# 20-Zigbee.net
KiCad netlist of a schematic drawn in Altium Designer
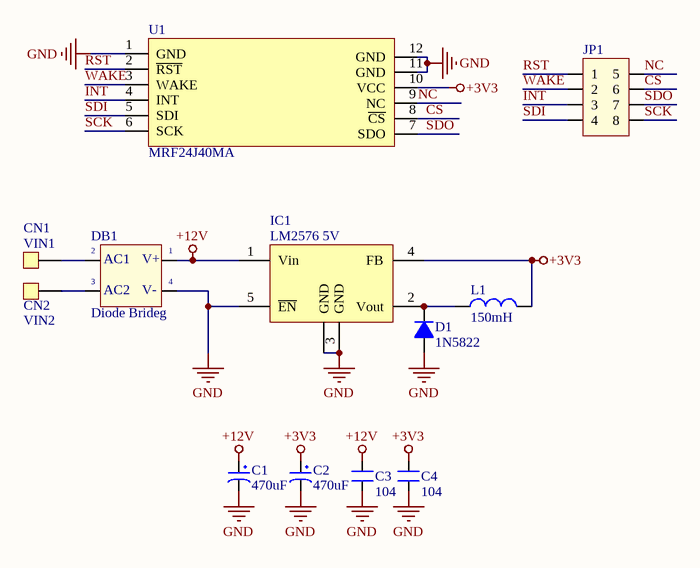
[diagram p0: 20-Zigbee.SchDoc]

(export (version "E")
  (design (tool "Eeschema 10.0.6"))
  (components
    (comp (ref "C1")
      (value "470uF")
      (footprint "C-TANT-7343-31-CASEA")
      (description "Cap P  0,1uF < 22uF , 16 - 50V")
      (libsource (lib "PART") (part "CP1"))
    )
    (comp (ref "C2")
      (value "470uF")
      (footprint "C-TANT-7343-31-CASEA")
      (description "Cap P  0,1uF < 22uF , 16 - 50V")
      (libsource (lib "PART") (part "CP1"))
    )
    (comp (ref "C3")
      (value "104")
      (footprint "C-0805")
      (fields (field (name "DESIGNED BY") "VanDungEvn"))
      (libsource (lib "syhaunguyen") (part "CN"))
    )
    (comp (ref "C4")
      (value "104")
      (footprint "C-0805")
      (fields (field (name "DESIGNED BY") "VanDungEvn"))
      (libsource (lib "syhaunguyen") (part "CN"))
    )
    (comp (ref "CN1")
      (value "VIN1")
      (footprint "M3")
      (libsource (lib "doAnTotNghiep2017Lib") (part "COCDONGM3"))
    )
    (comp (ref "CN2")
      (value "VIN2")
      (footprint "M3")
      (libsource (lib "doAnTotNghiep2017Lib") (part "COCDONGM3"))
    )
    (comp (ref "D1")
      (value "1N5822")
      (footprint "D-DO214-AB")
      (description "Diode 1A")
      (libsource (lib "PART") (part "D1A"))
    )
    (comp (ref "DB1")
      (value "Diode Brideg")
      (footprint "D-DB-1A-SMD")
      (description "Convert AC to DC voltage, 4 pin")
      (libsource (lib "PART") (part "DB"))
    )
    (comp (ref "IC1")
      (value "LM2576 5V")
      (footprint "TO-263-5L")
      (description "LM2576")
      (libsource (lib "PART") (part "LM2576"))
    )
    (comp (ref "JP1")
      (value "Connector 4x2")
      (footprint "JP4x2")
      (libsource (lib "syhaunguyen") (part "JP4x2"))
    )
    (comp (ref "L1")
      (value "150mH")
      (footprint "L-SMD-10x10")
      (description "Inductor")
      (libsource (lib "PART") (part "L1"))
    )
    (comp (ref "U1")
      (value "MRF24J40MA")
      (footprint "MRF24J40")
      (libsource (lib "MrQuan") (part "MRF24J40MA"))
    )
  )
  (nets
    (net (code "1") (name "+3V3") (class "Default")
      (node (ref "C2") (pin "1") (pinfunction "1_1") (pintype "passive"))
      (node (ref "C4") (pin "2") (pinfunction "2_2") (pintype "passive"))
      (node (ref "IC1") (pin "4") (pinfunction "FB_4") (pintype "passive"))
      (node (ref "L1") (pin "2") (pinfunction "2_2") (pintype "passive"))
      (node (ref "U1") (pin "10") (pinfunction "VCC_10") (pintype "passive"))
    )
    (net (code "2") (name "+12V") (class "Default")
      (node (ref "C1") (pin "1") (pinfunction "1_1") (pintype "passive"))
      (node (ref "C3") (pin "2") (pinfunction "2_2") (pintype "passive"))
      (node (ref "DB1") (pin "3") (pinfunction "AC2_3") (pintype "passive"))
      (node (ref "IC1") (pin "1") (pinfunction "Vin_1") (pintype "passive"))
    )
    (net (code "3") (name "/CS") (class "Default")
      (node (ref "JP1") (pin "6") (pinfunction "6_6") (pintype "passive"))
      (node (ref "U1") (pin "8") (pinfunction "~{CS}_8") (pintype "passive"))
    )
    (net (code "4") (name "/INT") (class "Default")
      (node (ref "JP1") (pin "3") (pinfunction "3_3") (pintype "passive"))
      (node (ref "U1") (pin "4") (pinfunction "INT_4") (pintype "passive"))
    )
    (net (code "5") (name "/NC") (class "Default")
      (node (ref "JP1") (pin "5") (pinfunction "5_5") (pintype "passive"))
      (node (ref "U1") (pin "9") (pinfunction "NC_9") (pintype "passive"))
    )
    (net (code "6") (name "/RST") (class "Default")
      (node (ref "JP1") (pin "1") (pinfunction "1_1") (pintype "passive"))
      (node (ref "U1") (pin "2") (pinfunction "~{RST}_2") (pintype "passive"))
    )
    (net (code "7") (name "/SCK") (class "Default")
      (node (ref "JP1") (pin "8") (pinfunction "8_8") (pintype "passive"))
      (node (ref "U1") (pin "6") (pinfunction "SCK_6") (pintype "passive"))
    )
    (net (code "8") (name "/SDI") (class "Default")
      (node (ref "JP1") (pin "4") (pinfunction "4_4") (pintype "passive"))
      (node (ref "U1") (pin "5") (pinfunction "SDI_5") (pintype "passive"))
    )
    (net (code "9") (name "/SDO") (class "Default")
      (node (ref "JP1") (pin "7") (pinfunction "7_7") (pintype "passive"))
      (node (ref "U1") (pin "7") (pinfunction "SDO_7") (pintype "passive"))
    )
    (net (code "10") (name "/WAKE") (class "Default")
      (node (ref "JP1") (pin "2") (pinfunction "2_2") (pintype "passive"))
      (node (ref "U1") (pin "3") (pinfunction "WAKE_3") (pintype "passive"))
    )
    (net (code "11") (name "GND") (class "Default")
      (node (ref "C1") (pin "2") (pinfunction "2_2") (pintype "passive"))
      (node (ref "C2") (pin "2") (pinfunction "2_2") (pintype "passive"))
      (node (ref "C3") (pin "1") (pinfunction "1_1") (pintype "passive"))
      (node (ref "C4") (pin "1") (pinfunction "1_1") (pintype "passive"))
      (node (ref "D1") (pin "1") (pinfunction "A_1") (pintype "passive"))
      (node (ref "DB1") (pin "4") (pinfunction "-V_OUT_4") (pintype "passive"))
      (node (ref "IC1") (pin "3") (pinfunction "GND_3") (pintype "passive"))
      (node (ref "IC1") (pin "5") (pinfunction "~{EN}_5") (pintype "passive"))
      (node (ref "IC1") (pin "HM") (pinfunction "GND_HM") (pintype "passive"))
      (node (ref "U1") (pin "1") (pinfunction "GND_1") (pintype "passive"))
      (node (ref "U1") (pin "11") (pinfunction "GND_11") (pintype "passive"))
      (node (ref "U1") (pin "12") (pinfunction "GND_12") (pintype "passive"))
    )
    (net (code "12") (name "Net-(D1-K)") (class "Default")
      (node (ref "D1") (pin "2") (pinfunction "K_2") (pintype "passive"))
      (node (ref "IC1") (pin "2") (pinfunction "Vout_2") (pintype "passive"))
      (node (ref "L1") (pin "1") (pinfunction "1_1") (pintype "passive"))
    )
    (net (code "13") (name "Net-(DB1-+V_OUT)") (class "Default")
      (node (ref "CN2") (pin "1") (pintype "passive"))
      (node (ref "DB1") (pin "1") (pinfunction "+V_OUT_1") (pintype "passive"))
    )
    (net (code "14") (name "Net-(DB1-AC1)") (class "Default")
      (node (ref "CN1") (pin "1") (pintype "passive"))
      (node (ref "DB1") (pin "2") (pinfunction "AC1_2") (pintype "passive"))
    )
  )
)
